# Power_Supply.net
KiCad netlist of a schematic drawn in Altium Designer
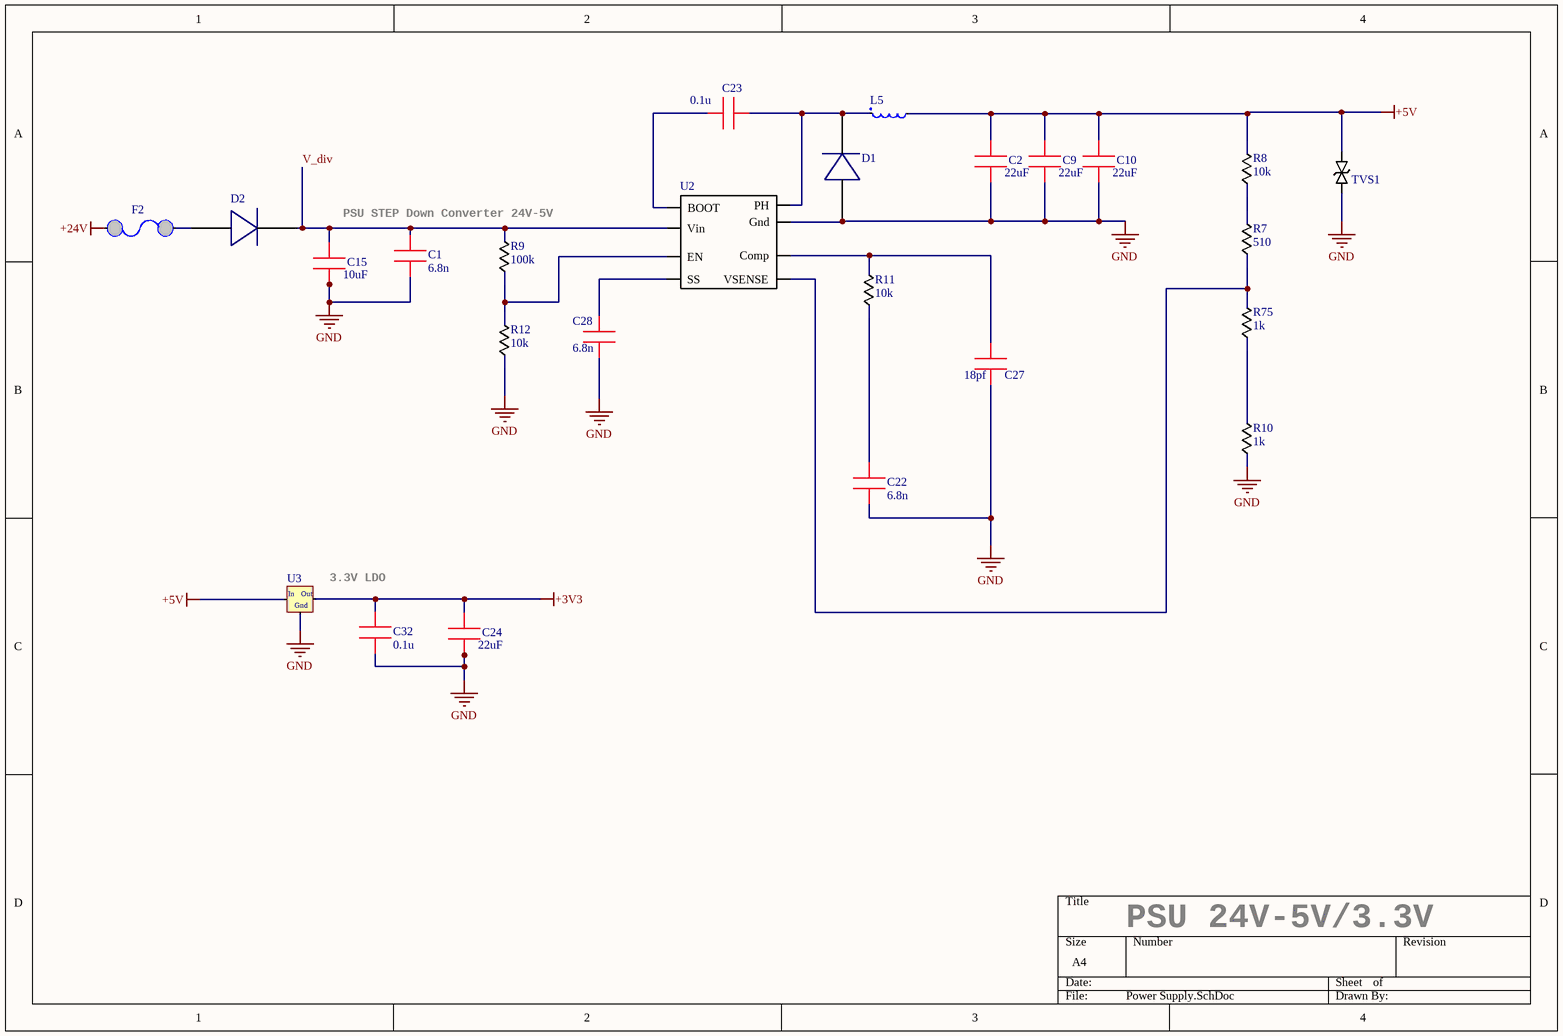
[diagram p0: Power Supply.SchDoc]

(export (version "E")
  (design (tool "Eeschema 10.0.6"))
  (components
    (comp (ref "C1")
      (value "6.8n")
      (footprint "0603")
      (fields (field (name "PART NUMBER") "CC0603KRX7R9BB682"))
      (libsource (lib "kontr") (part "0603 CAP"))
    )
    (comp (ref "C2")
      (value "22uF")
      (footprint "1206")
      (fields (field (name "PART NUMBER") "CC1206KKX5R7BB226"))
      (libsource (lib "kontr") (part "0805 Cap"))
    )
    (comp (ref "C9")
      (value "22uF")
      (footprint "1206")
      (fields (field (name "PART NUMBER") "CC1206KKX5R7BB226"))
      (libsource (lib "kontr") (part "0805 Cap"))
    )
    (comp (ref "C10")
      (value "22uF")
      (footprint "1206")
      (fields (field (name "PART NUMBER") "CC1206KKX5R7BB226"))
      (libsource (lib "kontr") (part "0805 Cap"))
    )
    (comp (ref "C15")
      (value "10uF")
      (footprint "1206")
      (fields (field (name "PART NUMBER") "GRM31CR61H106KA12L"))
      (libsource (lib "kontr") (part "0805 Cap"))
    )
    (comp (ref "C22")
      (value "6.8n")
      (footprint "0603")
      (fields (field (name "PART NUMBER") "CC0603KRX7R9BB682"))
      (libsource (lib "kontr") (part "0603 CAP"))
    )
    (comp (ref "C23")
      (value "0.1u")
      (footprint "0603")
      (fields (field (name "PART NUMBER") "GRM188R72A104KA35D"))
      (libsource (lib "kontr") (part "0805 Cap"))
    )
    (comp (ref "C24")
      (value "22uF")
      (footprint "1206")
      (fields (field (name "PART NUMBER") "CC1206KKX5R7BB226"))
      (libsource (lib "kontr") (part "0805 Cap"))
    )
    (comp (ref "C27")
      (value "18pf")
      (footprint "0603")
      (fields (field (name "PART NUMBER") "GRM1885C1H180JA01D"))
      (libsource (lib "kontr") (part "0805 Cap"))
    )
    (comp (ref "C28")
      (value "6.8n")
      (footprint "0603")
      (fields (field (name "PART NUMBER") "CC0603KRX7R9BB682"))
      (libsource (lib "kontr") (part "0805 Cap"))
    )
    (comp (ref "C32")
      (value "0.1u")
      (footprint "0603")
      (fields (field (name "PART NUMBER") "GRM188R72A104KA35D"))
      (libsource (lib "kontr") (part "Capasitor 0805"))
    )
    (comp (ref "D1")
      (value "~")
      (footprint "B340A-13-F")
      (fields (field (name "PART NUMBER") "B360A-13-F"))
      (libsource (lib "kontr") (part "B340A-13-F"))
    )
    (comp (ref "D2")
      (value "~")
      (footprint "B340A-13-F")
      (fields (field (name "PART NUMBER") "B360A-13-F"))
      (libsource (lib "kontr") (part "B340A-13-F"))
    )
    (comp (ref "F2")
      (value "~")
      (footprint "Fuse PTS")
      (fields (field (name "PART NUMBER") "MF-MSMF030-2"))
      (libsource (lib "kontr") (part "Fuse PTS"))
    )
    (comp (ref "L5")
      (value "~")
      (footprint "CDRH127/LDNP-270MC,")
      (fields (field (name "PART NUMBER") "CDRH127/LDNP-220MC"))
      (libsource (lib "kontr") (part "CDRH127/LDNP-270MC"))
    )
    (comp (ref "R7")
      (value "510")
      (footprint "0603")
      (fields (field (name "PART NUMBER") "RC0603JR-07510RL"))
      (libsource (lib "kontr") (part "Resistor 0805"))
    )
    (comp (ref "R8")
      (value "10k")
      (footprint "0603")
      (fields (field (name "PART NUMBER") "RC0603JR-0710K"))
      (libsource (lib "kontr") (part "Resistor 0805"))
    )
    (comp (ref "R9")
      (value "100k")
      (footprint "0603")
      (fields (field (name "PART NUMBER") "RC0603FR-07100KL"))
      (libsource (lib "kontr") (part "0603 RES"))
    )
    (comp (ref "R10")
      (value "1k")
      (footprint "0603")
      (fields (field (name "PART NUMBER") "RC0603JR-071KL"))
      (libsource (lib "kontr") (part "Resistor 0805"))
    )
    (comp (ref "R11")
      (value "10k")
      (footprint "0603")
      (fields (field (name "PART NUMBER") "RC0603JR-0710K"))
      (libsource (lib "kontr") (part "Resistor 0805"))
    )
    (comp (ref "R12")
      (value "10k")
      (footprint "0603")
      (fields (field (name "PART NUMBER") "RC0603JR-0710K"))
      (libsource (lib "kontr") (part "Resistor 0805"))
    )
    (comp (ref "R75")
      (value "1k")
      (footprint "0603")
      (fields (field (name "PART NUMBER") "RC0603JR-071KL"))
      (libsource (lib "kontr") (part "Resistor 0805"))
    )
    (comp (ref "TVS1")
      (value "~")
      (footprint "DO-214AC")
      (fields (field (name "PART NUMBER") "SMAJ5.0CA"))
      (libsource (lib "МЦТР.00010572.00.001") (part "TVS"))
    )
    (comp (ref "U2")
      (value "~")
      (footprint "SOIC 8")
      (fields (field (name "PART NUMBER") "TPS54331DR"))
      (libsource (lib "kontr") (part "TPS54331"))
    )
    (comp (ref "U3")
      (value "~")
      (footprint "SOT223")
      (fields (field (name "PART NUMBER") "LM1117MPX-3.3"))
      (libsource (lib "kontr") (part "NCV1117ST50T3G"))
    )
  )
  (nets
    (net (code "1") (name "+3V3") (class "Default")
      (node (ref "C24") (pin "2") (pinfunction "2_2") (pintype "passive"))
      (node (ref "C32") (pin "1") (pinfunction "1_1") (pintype "passive"))
      (node (ref "U3") (pin "2") (pinfunction "OUT_2") (pintype "passive"))
    )
    (net (code "2") (name "+5V") (class "Default")
      (node (ref "C10") (pin "2") (pinfunction "2_2") (pintype "passive"))
      (node (ref "C2") (pin "2") (pinfunction "2_2") (pintype "passive"))
      (node (ref "C9") (pin "2") (pinfunction "2_2") (pintype "passive"))
      (node (ref "L5") (pin "2") (pinfunction "2_2") (pintype "passive"))
      (node (ref "R8") (pin "2") (pintype "passive"))
      (node (ref "TVS1") (pin "2") (pinfunction "2_2") (pintype "passive"))
      (node (ref "U3") (pin "3") (pinfunction "IN_3") (pintype "passive"))
    )
    (net (code "3") (name "+24V") (class "Default")
      (node (ref "F2") (pin "2") (pinfunction "2_2") (pintype "passive"))
    )
    (net (code "4") (name "/V_div") (class "Default")
      (node (ref "C1") (pin "2") (pinfunction "2_2") (pintype "passive"))
      (node (ref "C15") (pin "2") (pinfunction "2_2") (pintype "passive"))
      (node (ref "D2") (pin "1") (pinfunction "1_1") (pintype "passive"))
      (node (ref "R9") (pin "2") (pintype "passive"))
      (node (ref "U2") (pin "2") (pinfunction "Vin_2") (pintype "passive"))
    )
    (net (code "5") (name "GND") (class "Default")
      (node (ref "C1") (pin "1") (pinfunction "1_1") (pintype "passive"))
      (node (ref "C10") (pin "1") (pinfunction "1_1") (pintype "passive"))
      (node (ref "C15") (pin "1") (pinfunction "1_1") (pintype "passive"))
      (node (ref "C2") (pin "1") (pinfunction "1_1") (pintype "passive"))
      (node (ref "C22") (pin "1") (pinfunction "1_1") (pintype "passive"))
      (node (ref "C24") (pin "1") (pinfunction "1_1") (pintype "passive"))
      (node (ref "C27") (pin "1") (pinfunction "1_1") (pintype "passive"))
      (node (ref "C28") (pin "1") (pinfunction "1_1") (pintype "passive"))
      (node (ref "C32") (pin "2") (pinfunction "2_2") (pintype "passive"))
      (node (ref "C9") (pin "1") (pinfunction "1_1") (pintype "passive"))
      (node (ref "D1") (pin "2") (pinfunction "1_2") (pintype "passive"))
      (node (ref "R10") (pin "1") (pintype "passive"))
      (node (ref "R12") (pin "1") (pintype "passive"))
      (node (ref "TVS1") (pin "1") (pinfunction "1_1") (pintype "passive"))
      (node (ref "U2") (pin "7") (pinfunction "Gnd_7") (pintype "passive"))
      (node (ref "U3") (pin "1") (pinfunction "GND_1") (pintype "passive"))
    )
    (net (code "6") (name "Net-(C22-Pad2)") (class "Default")
      (node (ref "C22") (pin "2") (pinfunction "2_2") (pintype "passive"))
      (node (ref "R11") (pin "1") (pintype "passive"))
    )
    (net (code "7") (name "Net-(D2-1-Pad2)") (class "Default")
      (node (ref "D2") (pin "2") (pinfunction "1_2") (pintype "passive"))
      (node (ref "F2") (pin "1") (pinfunction "1_1") (pintype "passive"))
    )
    (net (code "8") (name "Net-(R7-Pad2)") (class "Default")
      (node (ref "R7") (pin "2") (pintype "passive"))
      (node (ref "R8") (pin "1") (pintype "passive"))
    )
    (net (code "9") (name "Net-(R10-Pad2)") (class "Default")
      (node (ref "R10") (pin "2") (pintype "passive"))
      (node (ref "R75") (pin "1") (pintype "passive"))
    )
    (net (code "10") (name "Net-(U2-BOOT)") (class "Default")
      (node (ref "C23") (pin "1") (pinfunction "1_1") (pintype "passive"))
      (node (ref "U2") (pin "1") (pinfunction "BOOT_1") (pintype "passive"))
    )
    (net (code "11") (name "Net-(U2-Comp)") (class "Default")
      (node (ref "C27") (pin "2") (pinfunction "2_2") (pintype "passive"))
      (node (ref "R11") (pin "2") (pintype "passive"))
      (node (ref "U2") (pin "6") (pinfunction "Comp_6") (pintype "passive"))
    )
    (net (code "12") (name "Net-(U2-EN)") (class "Default")
      (node (ref "R12") (pin "2") (pintype "passive"))
      (node (ref "R9") (pin "1") (pintype "passive"))
      (node (ref "U2") (pin "3") (pinfunction "EN_3") (pintype "passive"))
    )
    (net (code "13") (name "Net-(U2-PH)") (class "Default")
      (node (ref "C23") (pin "2") (pinfunction "2_2") (pintype "passive"))
      (node (ref "D1") (pin "1") (pinfunction "1_1") (pintype "passive"))
      (node (ref "L5") (pin "1") (pinfunction "1_1") (pintype "passive"))
      (node (ref "U2") (pin "8") (pinfunction "PH_8") (pintype "passive"))
    )
    (net (code "14") (name "Net-(U2-SS)") (class "Default")
      (node (ref "C28") (pin "2") (pinfunction "2_2") (pintype "passive"))
      (node (ref "U2") (pin "4") (pinfunction "SS_4") (pintype "passive"))
    )
    (net (code "15") (name "Net-(U2-VSENSE)") (class "Default")
      (node (ref "R7") (pin "1") (pintype "passive"))
      (node (ref "R75") (pin "2") (pintype "passive"))
      (node (ref "U2") (pin "5") (pinfunction "VSENSE_5") (pintype "passive"))
    )
  )
)
